# 2voices_main.net
KiCad netlist of a schematic drawn in EAGLE
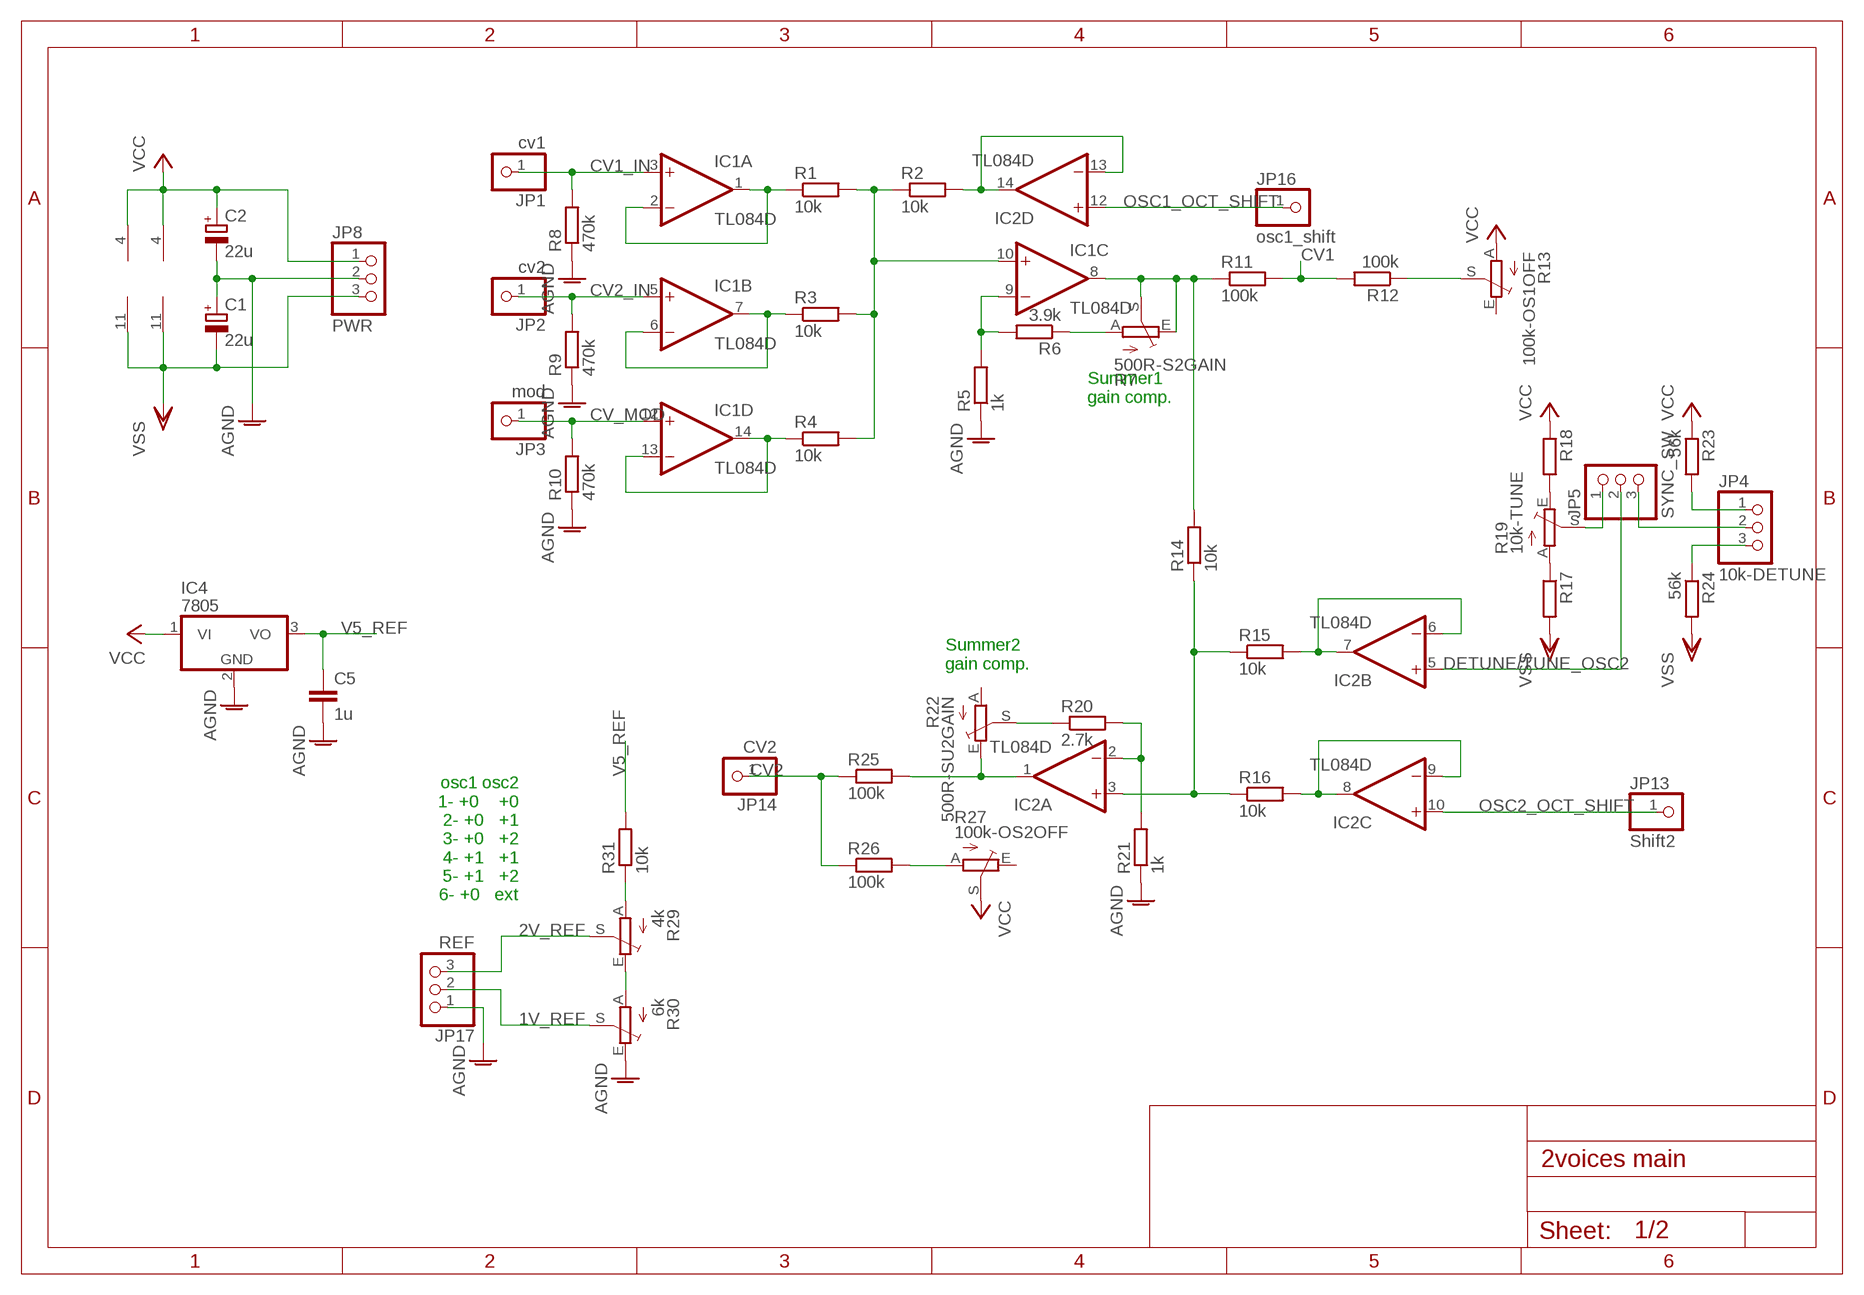
[diagram p0: schematic, sheet 1]
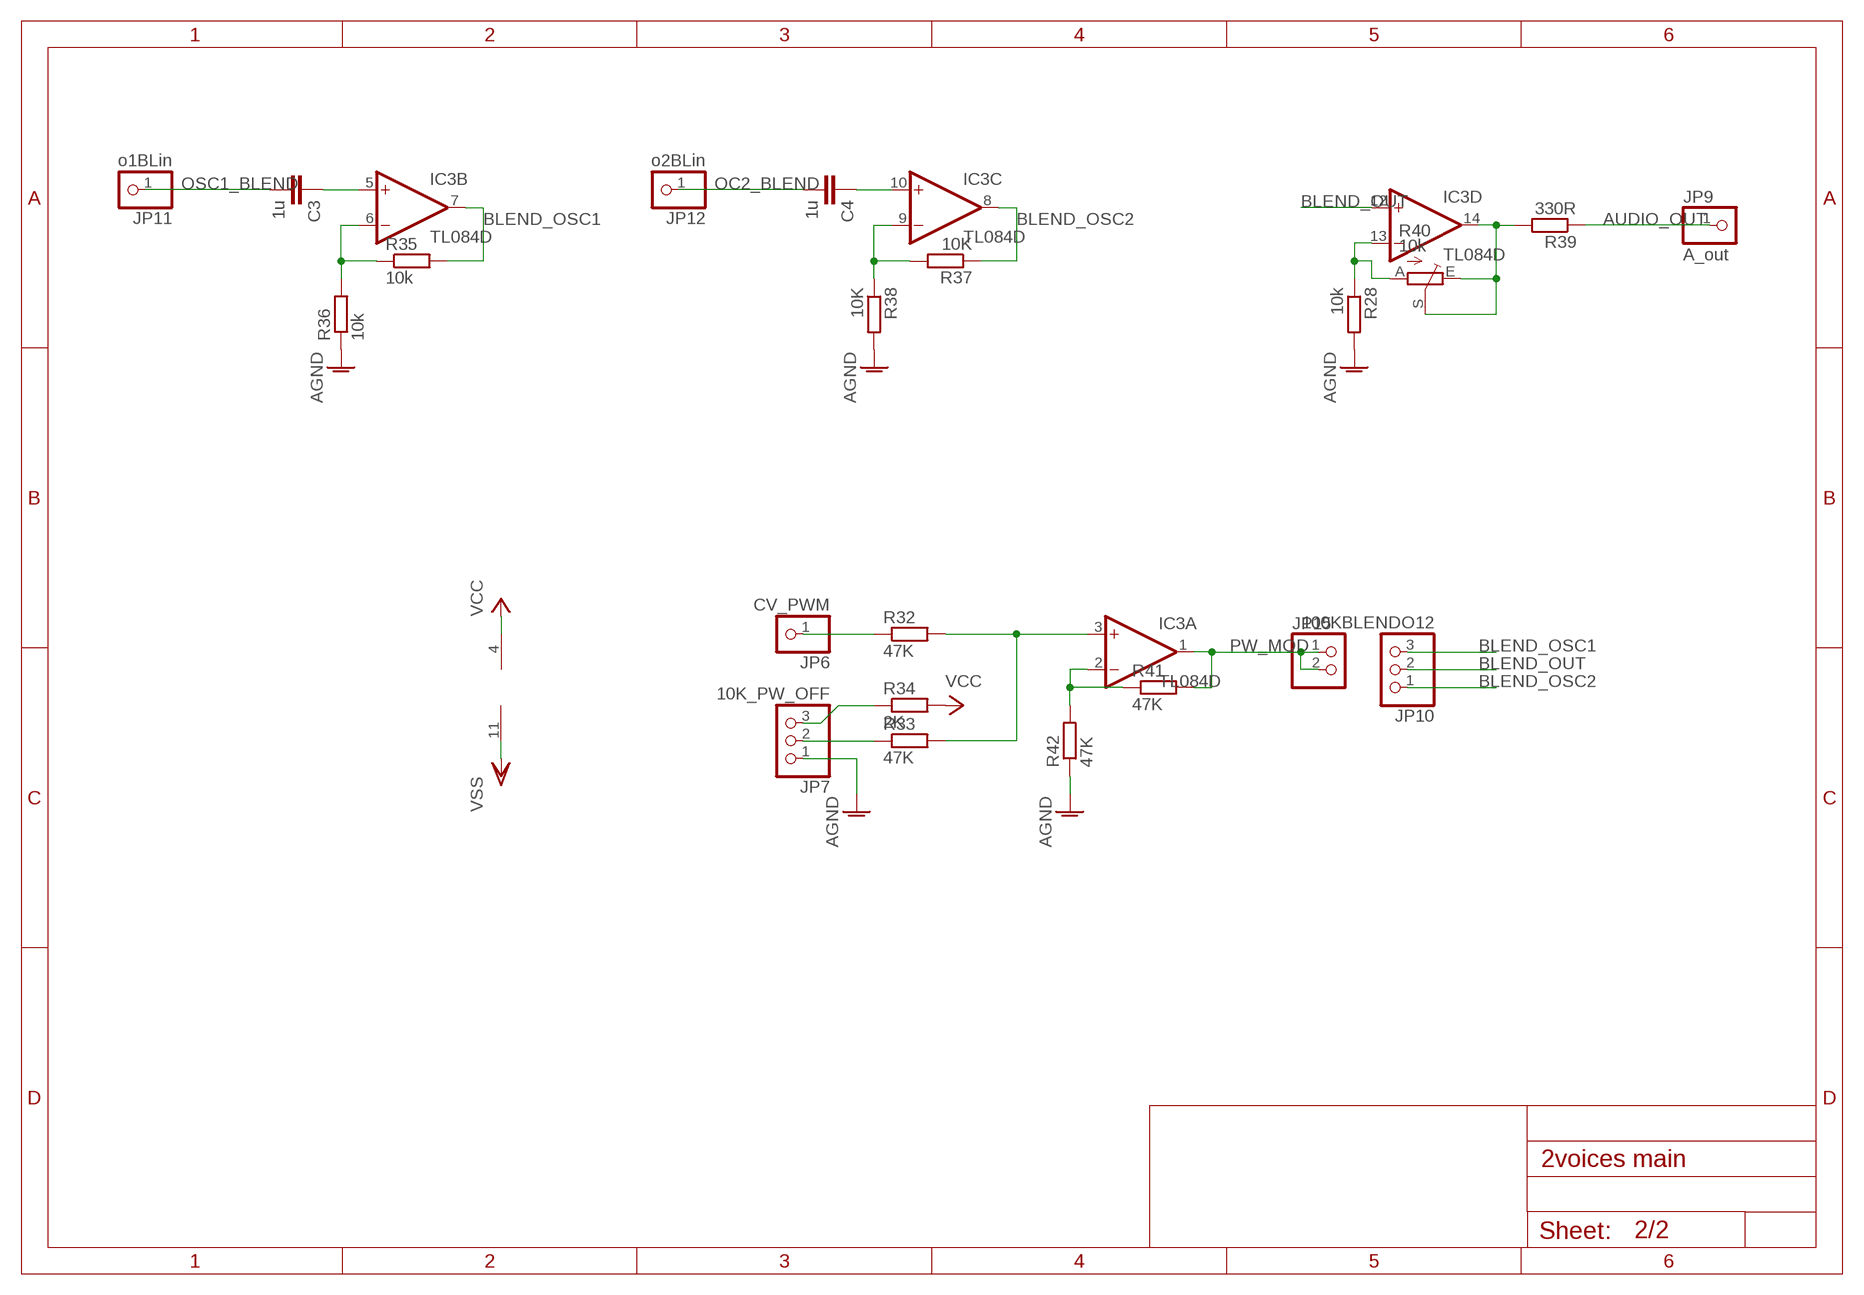
[diagram p1: schematic, sheet 2]

(export (version "E")
  (design (tool "Eeschema 10.0.6"))
  (components
    (comp (ref "C3")
      (value "1u")
      (footprint "eagle-import:C0805")
      (libsource (lib "eagle-import") (part "C-EUC0805"))
    )
    (comp (ref "C4")
      (value "1u")
      (footprint "eagle-import:C0805")
      (libsource (lib "eagle-import") (part "C-EUC0805"))
    )
    (comp (ref "IC3")
      (value "TL084D")
      (footprint "eagle-import:SO14")
      (libsource (lib "eagle-import") (part "TL084D"))
    )
    (comp (ref "JP6")
      (value "CV_PWM")
      (footprint "eagle-import:1X01")
      (libsource (lib "eagle-import") (part "PINHD-1X1"))
    )
    (comp (ref "JP7")
      (value "10K_PW_OFF")
      (footprint "eagle-import:1X03")
      (libsource (lib "eagle-import") (part "PINHD-1X3"))
    )
    (comp (ref "JP9")
      (value "A_out")
      (footprint "eagle-import:1X01")
      (libsource (lib "eagle-import") (part "PINHD-1X1"))
    )
    (comp (ref "JP10")
      (value "100KBLENDO12")
      (footprint "eagle-import:1X03")
      (libsource (lib "eagle-import") (part "PINHD-1X3"))
    )
    (comp (ref "JP11")
      (value "o1BLin")
      (footprint "eagle-import:1X01")
      (libsource (lib "eagle-import") (part "PINHD-1X1"))
    )
    (comp (ref "JP12")
      (value "o2BLin")
      (footprint "eagle-import:1X01")
      (libsource (lib "eagle-import") (part "PINHD-1X1"))
    )
    (comp (ref "JP15")
      (value "PINHD-1X2")
      (footprint "eagle-import:1X02")
      (libsource (lib "eagle-import") (part "PINHD-1X2"))
    )
    (comp (ref "R28")
      (value "10k")
      (footprint "eagle-import:R0805")
      (libsource (lib "eagle-import") (part "R-EU_R0805"))
    )
    (comp (ref "R32")
      (value "47K")
      (footprint "eagle-import:R0805")
      (libsource (lib "eagle-import") (part "R-EU_R0805"))
    )
    (comp (ref "R33")
      (value "47K")
      (footprint "eagle-import:R0805")
      (libsource (lib "eagle-import") (part "R-EU_R0805"))
    )
    (comp (ref "R34")
      (value "2K")
      (footprint "eagle-import:R0805")
      (libsource (lib "eagle-import") (part "R-EU_R0805"))
    )
    (comp (ref "R35")
      (value "10k")
      (footprint "eagle-import:R0805")
      (libsource (lib "eagle-import") (part "R-EU_R0805"))
    )
    (comp (ref "R36")
      (value "10k")
      (footprint "eagle-import:R0805")
      (libsource (lib "eagle-import") (part "R-EU_R0805"))
    )
    (comp (ref "R37")
      (value "10K")
      (footprint "eagle-import:R0805")
      (libsource (lib "eagle-import") (part "R-EU_R0805"))
    )
    (comp (ref "R38")
      (value "10K")
      (footprint "eagle-import:R0805")
      (libsource (lib "eagle-import") (part "R-EU_R0805"))
    )
    (comp (ref "R39")
      (value "330R")
      (footprint "eagle-import:R0805")
      (libsource (lib "eagle-import") (part "R-EU_R0805"))
    )
    (comp (ref "R40")
      (value "10k")
      (footprint "eagle-import:S63S")
      (libsource (lib "eagle-import") (part "TRIM_EU-S63S"))
    )
    (comp (ref "R41")
      (value "47K")
      (footprint "eagle-import:R0805")
      (libsource (lib "eagle-import") (part "R-EU_R0805"))
    )
    (comp (ref "R42")
      (value "47K")
      (footprint "eagle-import:R0805")
      (libsource (lib "eagle-import") (part "R-EU_R0805"))
    )
    (comp (ref "C1")
      (value "22u")
      (footprint "eagle-import:E2,5-7")
      (libsource (lib "eagle-import") (part "CPOL-EUE2.5-7"))
    )
    (comp (ref "C2")
      (value "22u")
      (footprint "eagle-import:E2,5-7")
      (libsource (lib "eagle-import") (part "CPOL-EUE2.5-7"))
    )
    (comp (ref "C5")
      (value "1u")
      (footprint "eagle-import:C0805")
      (libsource (lib "eagle-import") (part "C-EUC0805"))
    )
    (comp (ref "IC1")
      (value "TL084D")
      (footprint "eagle-import:SO14")
      (libsource (lib "eagle-import") (part "TL084D"))
    )
    (comp (ref "IC2")
      (value "TL084D")
      (footprint "eagle-import:SO14")
      (libsource (lib "eagle-import") (part "TL084D"))
    )
    (comp (ref "IC4")
      (value "7805")
      (footprint "eagle-import:TO220V")
      (libsource (lib "eagle-import") (part "78TV05"))
    )
    (comp (ref "JP1")
      (value "cv1")
      (footprint "eagle-import:1X01")
      (libsource (lib "eagle-import") (part "pinhead_PINHD-1X1"))
    )
    (comp (ref "JP2")
      (value "cv2")
      (footprint "eagle-import:1X01")
      (libsource (lib "eagle-import") (part "pinhead_PINHD-1X1"))
    )
    (comp (ref "JP3")
      (value "mod")
      (footprint "eagle-import:1X01")
      (libsource (lib "eagle-import") (part "pinhead_PINHD-1X1"))
    )
    (comp (ref "JP4")
      (value "10k-DETUNE")
      (footprint "eagle-import:1X03")
      (libsource (lib "eagle-import") (part "PINHD-1X3"))
    )
    (comp (ref "JP5")
      (value "SYNC_SW")
      (footprint "eagle-import:1X03")
      (libsource (lib "eagle-import") (part "PINHD-1X3"))
    )
    (comp (ref "JP8")
      (value "PWR")
      (footprint "eagle-import:1X03")
      (libsource (lib "eagle-import") (part "PINHD-1X3"))
    )
    (comp (ref "JP13")
      (value "Shift2")
      (footprint "eagle-import:1X01")
      (libsource (lib "eagle-import") (part "pinhead_PINHD-1X1"))
    )
    (comp (ref "JP14")
      (value "CV2")
      (footprint "eagle-import:1X01")
      (libsource (lib "eagle-import") (part "pinhead_PINHD-1X1"))
    )
    (comp (ref "JP16")
      (value "osc1_shift")
      (footprint "eagle-import:1X01")
      (libsource (lib "eagle-import") (part "pinhead_PINHD-1X1"))
    )
    (comp (ref "JP17")
      (value "REF")
      (footprint "eagle-import:1X03")
      (libsource (lib "eagle-import") (part "PINHD-1X3"))
    )
    (comp (ref "R1")
      (value "10k")
      (footprint "eagle-import:R0805")
      (libsource (lib "eagle-import") (part "R-EU_R0805"))
    )
    (comp (ref "R2")
      (value "10k")
      (footprint "eagle-import:R0805")
      (libsource (lib "eagle-import") (part "R-EU_R0805"))
    )
    (comp (ref "R3")
      (value "10k")
      (footprint "eagle-import:R0805")
      (libsource (lib "eagle-import") (part "R-EU_R0805"))
    )
    (comp (ref "R4")
      (value "10k")
      (footprint "eagle-import:R0805")
      (libsource (lib "eagle-import") (part "R-EU_R0805"))
    )
    (comp (ref "R5")
      (value "1k")
      (footprint "eagle-import:R0805")
      (libsource (lib "eagle-import") (part "R-EU_R0805"))
    )
    (comp (ref "R6")
      (value "3.9k")
      (footprint "eagle-import:R0805")
      (libsource (lib "eagle-import") (part "R-EU_R0805"))
    )
    (comp (ref "R7")
      (value "500R-S2GAIN")
      (footprint "eagle-import:S63S")
      (libsource (lib "eagle-import") (part "TRIM_EU-S63S"))
    )
    (comp (ref "R8")
      (value "470k")
      (footprint "eagle-import:R0805")
      (libsource (lib "eagle-import") (part "R-EU_R0805"))
    )
    (comp (ref "R9")
      (value "470k")
      (footprint "eagle-import:R0805")
      (libsource (lib "eagle-import") (part "R-EU_R0805"))
    )
    (comp (ref "R10")
      (value "470k")
      (footprint "eagle-import:R0805")
      (libsource (lib "eagle-import") (part "R-EU_R0805"))
    )
    (comp (ref "R11")
      (value "100k")
      (footprint "eagle-import:R0805")
      (libsource (lib "eagle-import") (part "R-EU_R0805"))
    )
    (comp (ref "R12")
      (value "100k")
      (footprint "eagle-import:R0805")
      (libsource (lib "eagle-import") (part "R-EU_R0805"))
    )
    (comp (ref "R13")
      (value "100k-OS1OFF")
      (footprint "eagle-import:S63S")
      (libsource (lib "eagle-import") (part "TRIM_EU-S63S"))
    )
    (comp (ref "R14")
      (value "10k")
      (footprint "eagle-import:R0805")
      (libsource (lib "eagle-import") (part "R-EU_R0805"))
    )
    (comp (ref "R15")
      (value "10k")
      (footprint "eagle-import:R0805")
      (libsource (lib "eagle-import") (part "R-EU_R0805"))
    )
    (comp (ref "R16")
      (value "10k")
      (footprint "eagle-import:R0805")
      (libsource (lib "eagle-import") (part "R-EU_R0805"))
    )
    (comp (ref "R17")
      (value "R-EU_R0805")
      (footprint "eagle-import:R0805")
      (libsource (lib "eagle-import") (part "R-EU_R0805"))
    )
    (comp (ref "R18")
      (value "R-EU_R0805")
      (footprint "eagle-import:R0805")
      (libsource (lib "eagle-import") (part "R-EU_R0805"))
    )
    (comp (ref "R19")
      (value "10k-TUNE")
      (footprint "eagle-import:S63S")
      (libsource (lib "eagle-import") (part "TRIM_EU-S63S"))
    )
    (comp (ref "R20")
      (value "2.7k")
      (footprint "eagle-import:R0805")
      (libsource (lib "eagle-import") (part "R-EU_R0805"))
    )
    (comp (ref "R21")
      (value "1k")
      (footprint "eagle-import:R0805")
      (libsource (lib "eagle-import") (part "R-EU_R0805"))
    )
    (comp (ref "R22")
      (value "500R-SU2GAIN")
      (footprint "eagle-import:S63S")
      (libsource (lib "eagle-import") (part "TRIM_EU-S63S"))
    )
    (comp (ref "R23")
      (value "56k")
      (footprint "eagle-import:R0805")
      (libsource (lib "eagle-import") (part "R-EU_R0805"))
    )
    (comp (ref "R24")
      (value "56k")
      (footprint "eagle-import:R0805")
      (libsource (lib "eagle-import") (part "R-EU_R0805"))
    )
    (comp (ref "R25")
      (value "100k")
      (footprint "eagle-import:R0805")
      (libsource (lib "eagle-import") (part "R-EU_R0805"))
    )
    (comp (ref "R26")
      (value "100k")
      (footprint "eagle-import:R0805")
      (libsource (lib "eagle-import") (part "R-EU_R0805"))
    )
    (comp (ref "R27")
      (value "100k-OS2OFF")
      (footprint "eagle-import:S63S")
      (libsource (lib "eagle-import") (part "TRIM_EU-S63S"))
    )
    (comp (ref "R29")
      (value "4k")
      (footprint "eagle-import:S63S")
      (libsource (lib "eagle-import") (part "TRIM_EU-S63S"))
    )
    (comp (ref "R30")
      (value "6k")
      (footprint "eagle-import:S63S")
      (libsource (lib "eagle-import") (part "TRIM_EU-S63S"))
    )
    (comp (ref "R31")
      (value "10k")
      (footprint "eagle-import:R0805")
      (libsource (lib "eagle-import") (part "R-EU_R0805"))
    )
  )
  (nets
    (net (code "1") (name "1V_REF") (class "Default")
      (node (ref "JP17") (pin "2") (pinfunction "2_2") (pintype "passive"))
      (node (ref "R30") (pin "S") (pinfunction "S_S") (pintype "passive"))
    )
    (net (code "2") (name "2V_REF") (class "Default")
      (node (ref "JP17") (pin "3") (pinfunction "3_3") (pintype "passive"))
      (node (ref "R29") (pin "S") (pinfunction "S_S") (pintype "passive"))
    )
    (net (code "3") (name "AGND") (class "Default")
      (node (ref "C1") (pin "+") (pinfunction "+_+") (pintype "passive"))
      (node (ref "C2") (pin "-") (pinfunction "-_-") (pintype "passive"))
      (node (ref "C5") (pin "2") (pinfunction "2_2") (pintype "passive"))
      (node (ref "IC4") (pin "2") (pinfunction "GND_2") (pintype "passive"))
      (node (ref "JP17") (pin "1") (pinfunction "1_1") (pintype "passive"))
      (node (ref "JP7") (pin "1") (pinfunction "1_1") (pintype "passive"))
      (node (ref "JP8") (pin "2") (pinfunction "2_2") (pintype "passive"))
      (node (ref "R10") (pin "1") (pinfunction "1_1") (pintype "passive"))
      (node (ref "R21") (pin "1") (pinfunction "1_1") (pintype "passive"))
      (node (ref "R28") (pin "2") (pinfunction "2_2") (pintype "passive"))
      (node (ref "R30") (pin "E") (pinfunction "E_E") (pintype "passive"))
      (node (ref "R36") (pin "1") (pinfunction "1_1") (pintype "passive"))
      (node (ref "R38") (pin "2") (pinfunction "2_2") (pintype "passive"))
      (node (ref "R42") (pin "1") (pinfunction "1_1") (pintype "passive"))
      (node (ref "R5") (pin "1") (pinfunction "1_1") (pintype "passive"))
      (node (ref "R8") (pin "1") (pinfunction "1_1") (pintype "passive"))
      (node (ref "R9") (pin "1") (pinfunction "1_1") (pintype "passive"))
    )
    (net (code "4") (name "AUDIO_OUT") (class "Default")
      (node (ref "JP9") (pin "1") (pinfunction "1_1") (pintype "passive"))
      (node (ref "R39") (pin "1") (pinfunction "1_1") (pintype "passive"))
    )
    (net (code "5") (name "BLEND_OSC1") (class "Default")
      (node (ref "IC3") (pin "7") (pinfunction "OUT_7") (pintype "output"))
      (node (ref "JP10") (pin "3") (pinfunction "3_3") (pintype "passive"))
      (node (ref "R35") (pin "2") (pinfunction "2_2") (pintype "passive"))
    )
    (net (code "6") (name "BLEND_OSC2") (class "Default")
      (node (ref "IC3") (pin "8") (pinfunction "OUT_8") (pintype "output"))
      (node (ref "JP10") (pin "1") (pinfunction "1_1") (pintype "passive"))
      (node (ref "R37") (pin "1") (pinfunction "1_1") (pintype "passive"))
    )
    (net (code "7") (name "BLEND_OUT") (class "Default")
      (node (ref "IC3") (pin "12") (pinfunction "+IN_12") (pintype "input"))
      (node (ref "JP10") (pin "2") (pinfunction "2_2") (pintype "passive"))
    )
    (net (code "8") (name "CV1") (class "Default")
      (node (ref "R11") (pin "2") (pinfunction "2_2") (pintype "passive"))
      (node (ref "R12") (pin "2") (pinfunction "2_2") (pintype "passive"))
    )
    (net (code "9") (name "CV1_IN") (class "Default")
      (node (ref "IC1") (pin "3") (pinfunction "+IN_3") (pintype "input"))
      (node (ref "JP1") (pin "1") (pinfunction "1_1") (pintype "passive"))
      (node (ref "R8") (pin "2") (pinfunction "2_2") (pintype "passive"))
    )
    (net (code "10") (name "CV2") (class "Default")
      (node (ref "JP14") (pin "1") (pinfunction "1_1") (pintype "passive"))
      (node (ref "R25") (pin "1") (pinfunction "1_1") (pintype "passive"))
      (node (ref "R26") (pin "1") (pinfunction "1_1") (pintype "passive"))
    )
    (net (code "11") (name "CV2_IN") (class "Default")
      (node (ref "IC1") (pin "5") (pinfunction "+IN_5") (pintype "input"))
      (node (ref "JP2") (pin "1") (pinfunction "1_1") (pintype "passive"))
      (node (ref "R9") (pin "2") (pinfunction "2_2") (pintype "passive"))
    )
    (net (code "12") (name "CV_MOD") (class "Default")
      (node (ref "IC1") (pin "12") (pinfunction "+IN_12") (pintype "input"))
      (node (ref "JP3") (pin "1") (pinfunction "1_1") (pintype "passive"))
      (node (ref "R10") (pin "2") (pinfunction "2_2") (pintype "passive"))
    )
    (net (code "13") (name "DETUNE{slash}TUNE_OSC2") (class "Default")
      (node (ref "IC2") (pin "5") (pinfunction "+IN_5") (pintype "input"))
      (node (ref "JP5") (pin "2") (pinfunction "2_2") (pintype "passive"))
    )
    (net (code "14") (name "Net-(IC1A--IN)") (class "Default")
      (node (ref "IC1") (pin "1") (pinfunction "OUT_1") (pintype "output"))
      (node (ref "IC1") (pin "2") (pinfunction "-IN_2") (pintype "input"))
      (node (ref "R1") (pin "1") (pinfunction "1_1") (pintype "passive"))
    )
    (net (code "15") (name "Net-(IC1B--IN)") (class "Default")
      (node (ref "IC1") (pin "6") (pinfunction "-IN_6") (pintype "input"))
      (node (ref "IC1") (pin "7") (pinfunction "OUT_7") (pintype "output"))
      (node (ref "R3") (pin "1") (pinfunction "1_1") (pintype "passive"))
    )
    (net (code "16") (name "Net-(IC1C-+IN)") (class "Default")
      (node (ref "IC1") (pin "10") (pinfunction "+IN_10") (pintype "input"))
      (node (ref "R1") (pin "2") (pinfunction "2_2") (pintype "passive"))
      (node (ref "R2") (pin "1") (pinfunction "1_1") (pintype "passive"))
      (node (ref "R3") (pin "2") (pinfunction "2_2") (pintype "passive"))
      (node (ref "R4") (pin "2") (pinfunction "2_2") (pintype "passive"))
    )
    (net (code "17") (name "Net-(IC1C--IN)") (class "Default")
      (node (ref "IC1") (pin "9") (pinfunction "-IN_9") (pintype "input"))
      (node (ref "R5") (pin "2") (pinfunction "2_2") (pintype "passive"))
      (node (ref "R6") (pin "2") (pinfunction "2_2") (pintype "passive"))
    )
    (net (code "18") (name "Net-(IC1C-OUT)") (class "Default")
      (node (ref "IC1") (pin "8") (pinfunction "OUT_8") (pintype "output"))
      (node (ref "R11") (pin "1") (pinfunction "1_1") (pintype "passive"))
      (node (ref "R14") (pin "2") (pinfunction "2_2") (pintype "passive"))
      (node (ref "R7") (pin "E") (pinfunction "E_E") (pintype "passive"))
      (node (ref "R7") (pin "S") (pinfunction "S_S") (pintype "passive"))
    )
    (net (code "19") (name "Net-(IC1D--IN)") (class "Default")
      (node (ref "IC1") (pin "13") (pinfunction "-IN_13") (pintype "input"))
      (node (ref "IC1") (pin "14") (pinfunction "OUT_14") (pintype "output"))
      (node (ref "R4") (pin "1") (pinfunction "1_1") (pintype "passive"))
    )
    (net (code "20") (name "Net-(IC2A-+IN)") (class "Default")
      (node (ref "IC2") (pin "3") (pinfunction "+IN_3") (pintype "input"))
      (node (ref "R14") (pin "1") (pinfunction "1_1") (pintype "passive"))
      (node (ref "R15") (pin "1") (pinfunction "1_1") (pintype "passive"))
      (node (ref "R16") (pin "1") (pinfunction "1_1") (pintype "passive"))
    )
    (net (code "21") (name "Net-(IC2A--IN)") (class "Default")
      (node (ref "IC2") (pin "2") (pinfunction "-IN_2") (pintype "input"))
      (node (ref "R20") (pin "2") (pinfunction "2_2") (pintype "passive"))
      (node (ref "R21") (pin "2") (pinfunction "2_2") (pintype "passive"))
    )
    (net (code "22") (name "Net-(IC2A-OUT)") (class "Default")
      (node (ref "IC2") (pin "1") (pinfunction "OUT_1") (pintype "output"))
      (node (ref "R22") (pin "E") (pinfunction "E_E") (pintype "passive"))
      (node (ref "R25") (pin "2") (pinfunction "2_2") (pintype "passive"))
    )
    (net (code "23") (name "Net-(IC2B--IN)") (class "Default")
      (node (ref "IC2") (pin "6") (pinfunction "-IN_6") (pintype "input"))
      (node (ref "IC2") (pin "7") (pinfunction "OUT_7") (pintype "output"))
      (node (ref "R15") (pin "2") (pinfunction "2_2") (pintype "passive"))
    )
    (net (code "24") (name "Net-(IC2C--IN)") (class "Default")
      (node (ref "IC2") (pin "8") (pinfunction "OUT_8") (pintype "output"))
      (node (ref "IC2") (pin "9") (pinfunction "-IN_9") (pintype "input"))
      (node (ref "R16") (pin "2") (pinfunction "2_2") (pintype "passive"))
    )
    (net (code "25") (name "Net-(IC2D--IN)") (class "Default")
      (node (ref "IC2") (pin "13") (pinfunction "-IN_13") (pintype "input"))
      (node (ref "IC2") (pin "14") (pinfunction "OUT_14") (pintype "output"))
      (node (ref "R2") (pin "2") (pinfunction "2_2") (pintype "passive"))
    )
    (net (code "26") (name "Net-(IC3A-+IN)") (class "Default")
      (node (ref "IC3") (pin "3") (pinfunction "+IN_3") (pintype "input"))
      (node (ref "R32") (pin "2") (pinfunction "2_2") (pintype "passive"))
      (node (ref "R33") (pin "2") (pinfunction "2_2") (pintype "passive"))
    )
    (net (code "27") (name "Net-(IC3A--IN)") (class "Default")
      (node (ref "IC3") (pin "2") (pinfunction "-IN_2") (pintype "input"))
      (node (ref "R41") (pin "1") (pinfunction "1_1") (pintype "passive"))
      (node (ref "R42") (pin "2") (pinfunction "2_2") (pintype "passive"))
    )
    (net (code "28") (name "Net-(IC3B-+IN)") (class "Default")
      (node (ref "C3") (pin "1") (pinfunction "1_1") (pintype "passive"))
      (node (ref "IC3") (pin "5") (pinfunction "+IN_5") (pintype "input"))
    )
    (net (code "29") (name "Net-(IC3B--IN)") (class "Default")
      (node (ref "IC3") (pin "6") (pinfunction "-IN_6") (pintype "input"))
      (node (ref "R35") (pin "1") (pinfunction "1_1") (pintype "passive"))
      (node (ref "R36") (pin "2") (pinfunction "2_2") (pintype "passive"))
    )
    (net (code "30") (name "Net-(IC3C-+IN)") (class "Default")
      (node (ref "C4") (pin "1") (pinfunction "1_1") (pintype "passive"))
      (node (ref "IC3") (pin "10") (pinfunction "+IN_10") (pintype "input"))
    )
    (net (code "31") (name "Net-(IC3C--IN)") (class "Default")
      (node (ref "IC3") (pin "9") (pinfunction "-IN_9") (pintype "input"))
      (node (ref "R37") (pin "2") (pinfunction "2_2") (pintype "passive"))
      (node (ref "R38") (pin "1") (pinfunction "1_1") (pintype "passive"))
    )
    (net (code "32") (name "Net-(IC3D--IN)") (class "Default")
      (node (ref "IC3") (pin "13") (pinfunction "-IN_13") (pintype "input"))
      (node (ref "R28") (pin "1") (pinfunction "1_1") (pintype "passive"))
      (node (ref "R40") (pin "A") (pinfunction "A_A") (pintype "passive"))
    )
    (net (code "33") (name "Net-(IC3D-OUT)") (class "Default")
      (node (ref "IC3") (pin "14") (pinfunction "OUT_14") (pintype "output"))
      (node (ref "R39") (pin "2") (pinfunction "2_2") (pintype "passive"))
      (node (ref "R40") (pin "E") (pinfunction "E_E") (pintype "passive"))
      (node (ref "R40") (pin "S") (pinfunction "S_S") (pintype "passive"))
    )
    (net (code "34") (name "Net-(JP4-Pad1)") (class "Default")
      (node (ref "JP4") (pin "1") (pinfunction "1_1") (pintype "passive"))
      (node (ref "R23") (pin "2") (pinfunction "2_2") (pintype "passive"))
    )
    (net (code "35") (name "Net-(JP4-Pad2)") (class "Default")
      (node (ref "JP4") (pin "2") (pinfunction "2_2") (pintype "passive"))
      (node (ref "JP5") (pin "3") (pinfunction "3_3") (pintype "passive"))
    )
    (net (code "36") (name "Net-(JP4-Pad3)") (class "Default")
      (node (ref "JP4") (pin "3") (pinfunction "3_3") (pintype "passive"))
      (node (ref "R24") (pin "1") (pinfunction "1_1") (pintype "passive"))
    )
    (net (code "37") (name "Net-(JP5-Pad1)") (class "Default")
      (node (ref "JP5") (pin "1") (pinfunction "1_1") (pintype "passive"))
      (node (ref "R19") (pin "S") (pinfunction "S_S") (pintype "passive"))
    )
    (net (code "38") (name "Net-(JP6-Pad1)") (class "Default")
      (node (ref "JP6") (pin "1") (pinfunction "1_1") (pintype "passive"))
      (node (ref "R32") (pin "1") (pinfunction "1_1") (pintype "passive"))
    )
    (net (code "39") (name "Net-(JP7-Pad2)") (class "Default")
      (node (ref "JP7") (pin "2") (pinfunction "2_2") (pintype "passive"))
      (node (ref "R33") (pin "1") (pinfunction "1_1") (pintype "passive"))
    )
    (net (code "40") (name "Net-(JP7-Pad3)") (class "Default")
      (node (ref "JP7") (pin "3") (pinfunction "3_3") (pintype "passive"))
      (node (ref "R34") (pin "1") (pinfunction "1_1") (pintype "passive"))
    )
    (net (code "41") (name "Net-(R6-Pad1)") (class "Default")
      (node (ref "R6") (pin "1") (pinfunction "1_1") (pintype "passive"))
      (node (ref "R7") (pin "A") (pinfunction "A_A") (pintype "passive"))
    )
    (net (code "42") (name "Net-(R12-Pad1)") (class "Default")
      (node (ref "R12") (pin "1") (pinfunction "1_1") (pintype "passive"))
      (node (ref "R13") (pin "S") (pinfunction "S_S") (pintype "passive"))
    )
    (net (code "43") (name "Net-(R17-Pad1)") (class "Default")
      (node (ref "R17") (pin "1") (pinfunction "1_1") (pintype "passive"))
      (node (ref "R19") (pin "A") (pinfunction "A_A") (pintype "passive"))
    )
    (net (code "44") (name "Net-(R18-Pad2)") (class "Default")
      (node (ref "R18") (pin "2") (pinfunction "2_2") (pintype "passive"))
      (node (ref "R19") (pin "E") (pinfunction "E_E") (pintype "passive"))
    )
    (net (code "45") (name "Net-(R20-Pad1)") (class "Default")
      (node (ref "R20") (pin "1") (pinfunction "1_1") (pintype "passive"))
      (node (ref "R22") (pin "S") (pinfunction "S_S") (pintype "passive"))
    )
    (net (code "46") (name "Net-(R26-Pad2)") (class "Default")
      (node (ref "R26") (pin "2") (pinfunction "2_2") (pintype "passive"))
      (node (ref "R27") (pin "A") (pinfunction "A_A") (pintype "passive"))
    )
    (net (code "47") (name "Net-(R29-PadA)") (class "Default")
      (node (ref "R29") (pin "A") (pinfunction "A_A") (pintype "passive"))
      (node (ref "R31") (pin "1") (pinfunction "1_1") (pintype "passive"))
    )
    (net (code "48") (name "Net-(R29-PadE)") (class "Default")
      (node (ref "R29") (pin "E") (pinfunction "E_E") (pintype "passive"))
      (node (ref "R30") (pin "A") (pinfunction "A_A") (pintype "passive"))
    )
    (net (code "49") (name "OC2_BLEND") (class "Default")
      (node (ref "C4") (pin "2") (pinfunction "2_2") (pintype "passive"))
      (node (ref "JP12") (pin "1") (pinfunction "1_1") (pintype "passive"))
    )
    (net (code "50") (name "OSC1_BLEND") (class "Default")
      (node (ref "C3") (pin "2") (pinfunction "2_2") (pintype "passive"))
      (node (ref "JP11") (pin "1") (pinfunction "1_1") (pintype "passive"))
    )
    (net (code "51") (name "OSC1_OCT_SHIFT") (class "Default")
      (node (ref "IC2") (pin "12") (pinfunction "+IN_12") (pintype "input"))
      (node (ref "JP16") (pin "1") (pinfunction "1_1") (pintype "passive"))
    )
    (net (code "52") (name "OSC2_OCT_SHIFT") (class "Default")
      (node (ref "IC2") (pin "10") (pinfunction "+IN_10") (pintype "input"))
      (node (ref "JP13") (pin "1") (pinfunction "1_1") (pintype "passive"))
    )
    (net (code "53") (name "PW_MOD") (class "Default")
      (node (ref "IC3") (pin "1") (pinfunction "OUT_1") (pintype "output"))
      (node (ref "JP15") (pin "1") (pinfunction "1_1") (pintype "passive"))
      (node (ref "JP15") (pin "2") (pinfunction "2_2") (pintype "passive"))
      (node (ref "R41") (pin "2") (pinfunction "2_2") (pintype "passive"))
    )
    (net (code "54") (name "V5_REF") (class "Default")
      (node (ref "C5") (pin "1") (pinfunction "1_1") (pintype "passive"))
      (node (ref "IC4") (pin "3") (pinfunction "VO_3") (pintype "passive"))
      (node (ref "R31") (pin "2") (pinfunction "2_2") (pintype "passive"))
    )
    (net (code "55") (name "VCC") (class "Default")
      (node (ref "C2") (pin "+") (pinfunction "+_+") (pintype "passive"))
      (node (ref "IC1") (pin "4") (pinfunction "V+_4") (pintype "power_in"))
      (node (ref "IC2") (pin "4") (pinfunction "V+_4") (pintype "power_in"))
      (node (ref "IC3") (pin "4") (pinfunction "V+_4") (pintype "power_in"))
      (node (ref "IC4") (pin "1") (pinfunction "VI_1") (pintype "input"))
      (node (ref "JP8") (pin "1") (pinfunction "1_1") (pintype "passive"))
      (node (ref "R13") (pin "A") (pinfunction "A_A") (pintype "passive"))
      (node (ref "R18") (pin "1") (pinfunction "1_1") (pintype "passive"))
      (node (ref "R23") (pin "1") (pinfunction "1_1") (pintype "passive"))
      (node (ref "R27") (pin "S") (pinfunction "S_S") (pintype "passive"))
      (node (ref "R34") (pin "2") (pinfunction "2_2") (pintype "passive"))
    )
    (net (code "56") (name "VSS") (class "Default")
      (node (ref "C1") (pin "-") (pinfunction "-_-") (pintype "passive"))
      (node (ref "IC1") (pin "11") (pinfunction "V-_11") (pintype "power_in"))
      (node (ref "IC2") (pin "11") (pinfunction "V-_11") (pintype "power_in"))
      (node (ref "IC3") (pin "11") (pinfunction "V-_11") (pintype "power_in"))
      (node (ref "JP8") (pin "3") (pinfunction "3_3") (pintype "passive"))
      (node (ref "R17") (pin "2") (pinfunction "2_2") (pintype "passive"))
      (node (ref "R24") (pin "2") (pinfunction "2_2") (pintype "passive"))
    )
    (net (code "57") (name "unconnected-(R13-PadE)") (class "Default")
      (node (ref "R13") (pin "E") (pinfunction "E_E") (pintype "passive"))
    )
    (net (code "58") (name "unconnected-(R22-PadA)") (class "Default")
      (node (ref "R22") (pin "A") (pinfunction "A_A") (pintype "passive"))
    )
    (net (code "59") (name "unconnected-(R27-PadE)") (class "Default")
      (node (ref "R27") (pin "E") (pinfunction "E_E") (pintype "passive"))
    )
  )
)
